# schV2_2.net
KiCad netlist of a schematic drawn in EAGLE
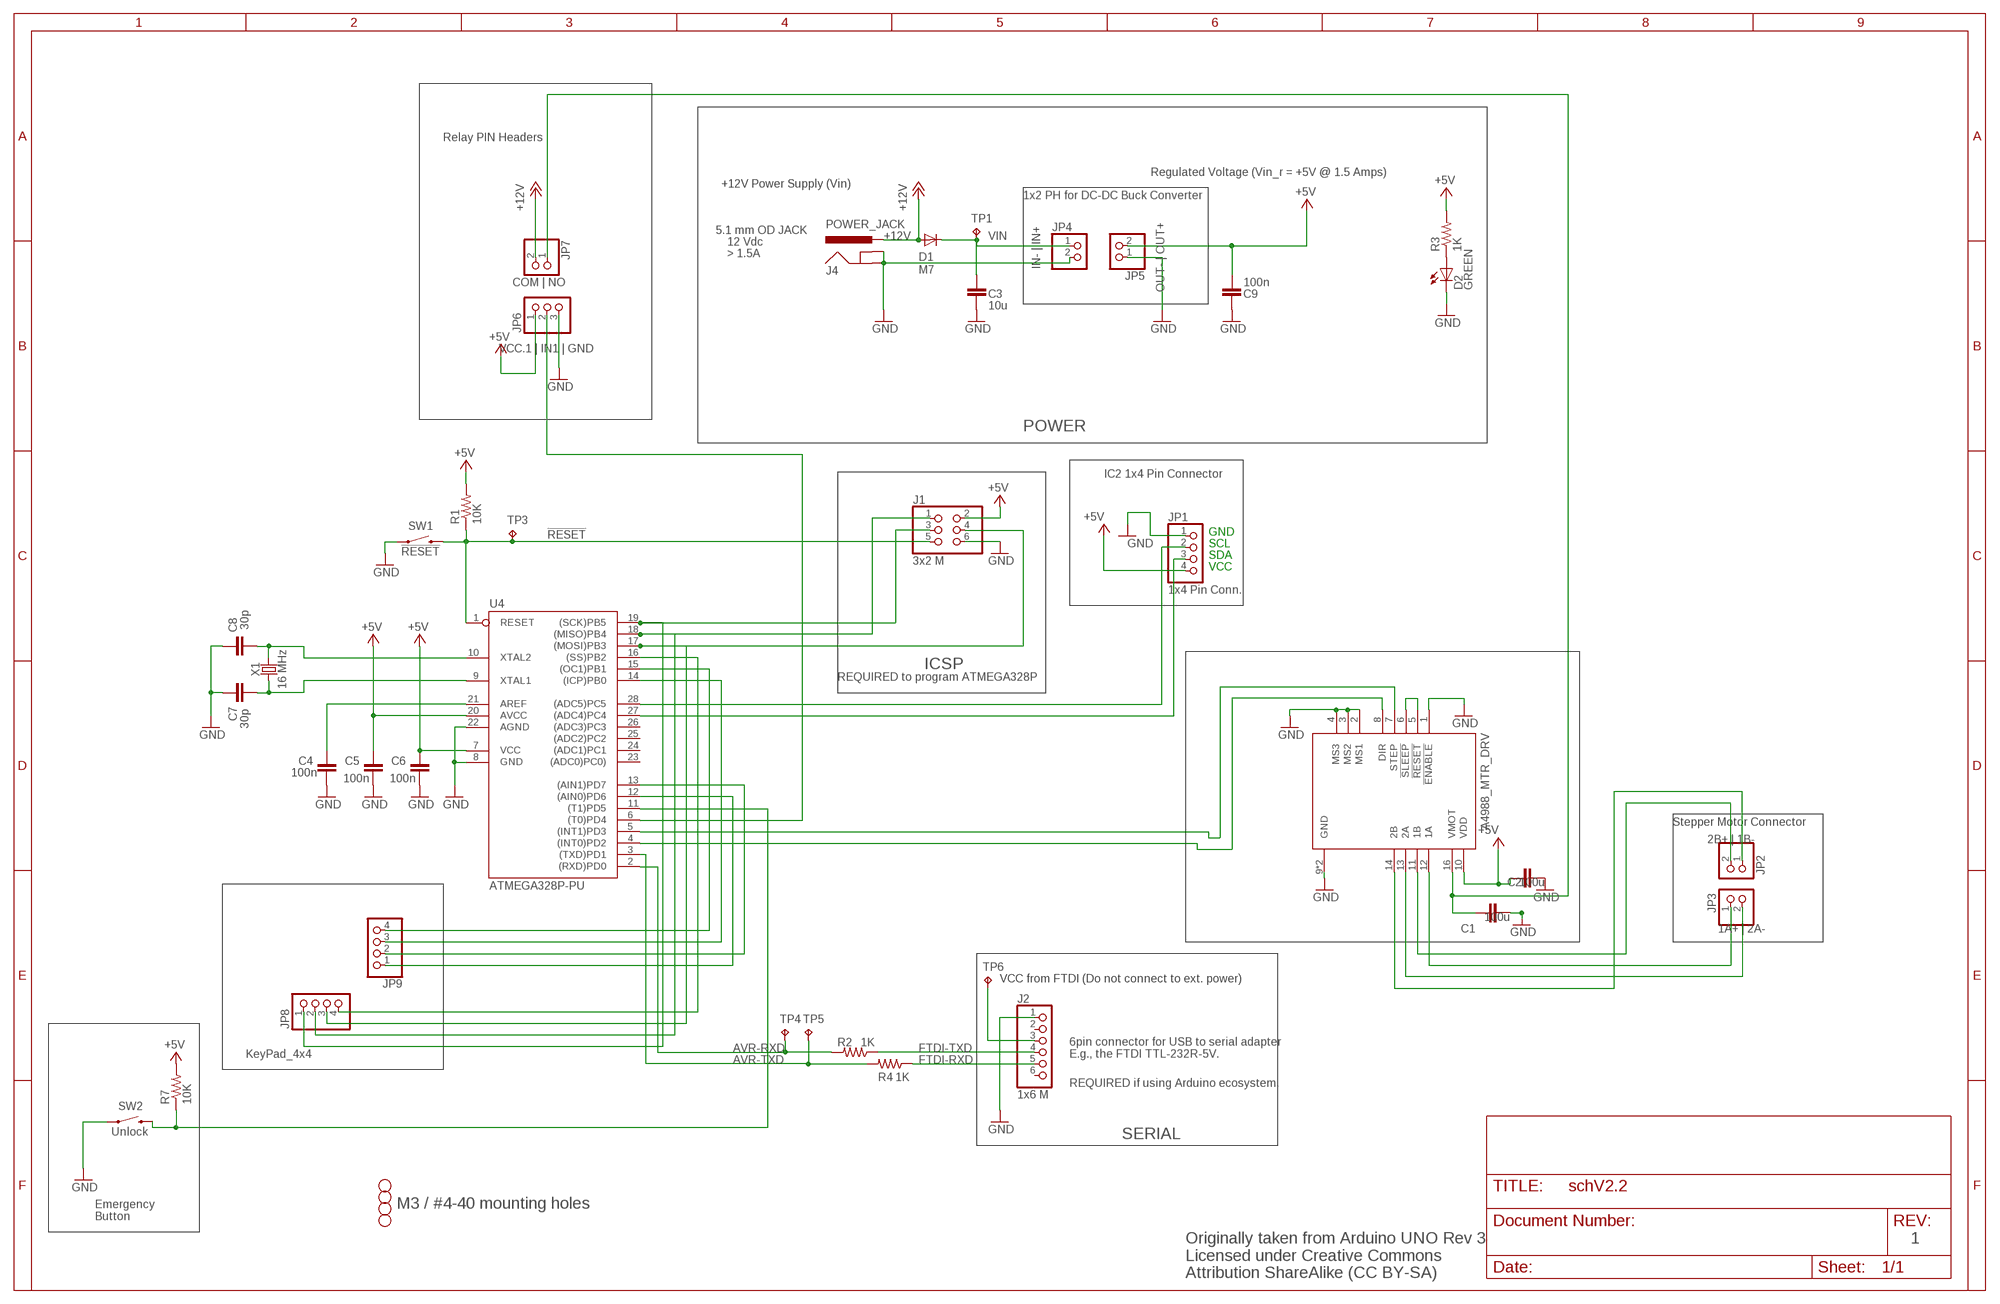
[diagram p0: schematic, sheet 1]

(export (version "E")
  (design (tool "Eeschema 10.0.6"))
  (components
    (comp (ref "A4988_MTR_DRV")
      (value "A4988_STEPPER_MOTOR_DRIVER_CARRIER")
      (footprint "eagle-import:MODULE_A4988_STEPPER_MOTOR_DRIVER_CARRIER")
      (fields (field (name "MF") "Pololu") (field (name "MP") "A4988 STEPPER MOTOR DRIVER CARRIER"))
      (libsource (lib "eagle-import") (part "A4988_STEPPER_MOTOR_DRIVER_CARRIER"))
    )
    (comp (ref "C1")
      (value "100u")
      (footprint "eagle-import:C0805K")
      (fields (field (name "MFR") "Samsung") (field (name "MPN") "CL21B104KBCNNNC"))
      (libsource (lib "eagle-import") (part "C-EUC0805K"))
    )
    (comp (ref "C2")
      (value "100u")
      (footprint "eagle-import:C0805K")
      (fields (field (name "MFR") "Samsung") (field (name "MPN") "CL21B104KBCNNNC"))
      (libsource (lib "eagle-import") (part "C-EUC0805K"))
    )
    (comp (ref "C3")
      (value "10u")
      (footprint "eagle-import:C0805K")
      (fields (field (name "MFR") "Samsung") (field (name "MPN") "CL21A106KOQNNNG"))
      (libsource (lib "eagle-import") (part "C-EUC0805K"))
    )
    (comp (ref "C4")
      (value "100n")
      (footprint "eagle-import:C0805K")
      (fields (field (name "MFR") "Samsung") (field (name "MPN") "CL21B104KBCNNNC"))
      (libsource (lib "eagle-import") (part "C-EUC0805K"))
    )
    (comp (ref "C5")
      (value "100n")
      (footprint "eagle-import:C0805K")
      (fields (field (name "MFR") "Samsung") (field (name "MPN") "CL21B104KBCNNNC"))
      (libsource (lib "eagle-import") (part "C-EUC0805K"))
    )
    (comp (ref "C6")
      (value "100n")
      (footprint "eagle-import:C0805K")
      (fields (field (name "MFR") "Samsung") (field (name "MPN") "CL21B104KBCNNNC"))
      (libsource (lib "eagle-import") (part "C-EUC0805K"))
    )
    (comp (ref "C7")
      (value "30p")
      (footprint "eagle-import:C0805K")
      (fields (field (name "MFR") "Samsung") (field (name "MPN") "CL21C180JBANNNC"))
      (libsource (lib "eagle-import") (part "C-EUC0805K"))
    )
    (comp (ref "C8")
      (value "30p")
      (footprint "eagle-import:C0805K")
      (fields (field (name "MFR") "Samsung") (field (name "MPN") "CL21C300JBANNNC"))
      (libsource (lib "eagle-import") (part "C-EUC0805K"))
    )
    (comp (ref "C9")
      (value "100n")
      (footprint "eagle-import:C0805K")
      (fields (field (name "MFR") "Samsung") (field (name "MPN") "CL21B104KBCNNNC"))
      (libsource (lib "eagle-import") (part "C-EUC0805K"))
    )
    (comp (ref "D1")
      (value "M7")
      (footprint "eagle-import:SMB")
      (fields (field (name "MFR") "SMC Diode") (field (name "MPN") "10BQ030TR"))
      (libsource (lib "eagle-import") (part "DIODE-SMB"))
    )
    (comp (ref "D2")
      (value "GREEN")
      (footprint "eagle-import:CHIP-LED0805")
      (fields (field (name "MFR") "Würth Elektronik") (field (name "MPN") "150080GS75000"))
      (libsource (lib "eagle-import") (part "LEDCHIP-LED0805"))
    )
    (comp (ref "H1")
      (value "STAND-OFF")
      (footprint "eagle-import:STAND-OFF")
      (libsource (lib "eagle-import") (part "STAND-OFF"))
    )
    (comp (ref "H2")
      (value "STAND-OFF")
      (footprint "eagle-import:STAND-OFF")
      (libsource (lib "eagle-import") (part "STAND-OFF"))
    )
    (comp (ref "H3")
      (value "STAND-OFF")
      (footprint "eagle-import:STAND-OFF")
      (libsource (lib "eagle-import") (part "STAND-OFF"))
    )
    (comp (ref "H4")
      (value "STAND-OFF")
      (footprint "eagle-import:STAND-OFF")
      (libsource (lib "eagle-import") (part "STAND-OFF"))
    )
    (comp (ref "J1")
      (value "3x2 M")
      (footprint "eagle-import:2X03")
      (fields (field (name "MFR") "Harwin") (field (name "MPN") "M20-9980345"))
      (libsource (lib "eagle-import") (part "PINHD-2X3"))
    )
    (comp (ref "J2")
      (value "1x6 M")
      (footprint "eagle-import:1X06")
      (fields (field (name "MFR") "Sullins") (field (name "MPN") "PRPC006SAAN-RC"))
      (libsource (lib "eagle-import") (part "PINHD-1X6"))
    )
    (comp (ref "J4")
      (value "POWER_JACK")
      (footprint "eagle-import:POWER_JACK_PTH")
      (fields (field (name "MFR") "CUI") (field (name "MPN") "PJ-202A"))
      (libsource (lib "eagle-import") (part "POWER_JACK"))
    )
    (comp (ref "JP1")
      (value "1x4 Pin Conn.")
      (footprint "eagle-import:1X04")
      (libsource (lib "eagle-import") (part "PINHD-1X4"))
    )
    (comp (ref "JP2")
      (value "2B+ | 1B-")
      (footprint "eagle-import:1X02")
      (libsource (lib "eagle-import") (part "PINHD-1X2"))
    )
    (comp (ref "JP3")
      (value "1A+ | 2A-")
      (footprint "eagle-import:1X02")
      (libsource (lib "eagle-import") (part "PINHD-1X2"))
    )
    (comp (ref "JP4")
      (value "IN- | IN+")
      (footprint "eagle-import:1X02")
      (libsource (lib "eagle-import") (part "PINHD-1X2"))
    )
    (comp (ref "JP5")
      (value "OUT- | OUT+")
      (footprint "eagle-import:1X02")
      (libsource (lib "eagle-import") (part "PINHD-1X2"))
    )
    (comp (ref "JP6")
      (value "VCC.1 | IN1 | GND")
      (footprint "eagle-import:1X03")
      (libsource (lib "eagle-import") (part "PINHD-1X3"))
    )
    (comp (ref "JP7")
      (value "COM | NO")
      (footprint "eagle-import:1X02")
      (libsource (lib "eagle-import") (part "PINHD-1X2"))
    )
    (comp (ref "JP8")
      (value "PINHD-1X4")
      (footprint "eagle-import:1X04")
      (libsource (lib "eagle-import") (part "PINHD-1X4"))
    )
    (comp (ref "JP9")
      (value "PINHD-1X4")
      (footprint "eagle-import:1X04")
      (libsource (lib "eagle-import") (part "PINHD-1X4"))
    )
    (comp (ref "R1")
      (value "10K")
      (footprint "eagle-import:R0805")
      (fields (field (name "MFR") "Yageo") (field (name "MPN") "RC0805FR-0710KL"))
      (libsource (lib "eagle-import") (part "R-US_R0805"))
    )
    (comp (ref "R2")
      (value "1K")
      (footprint "eagle-import:R0805")
      (fields (field (name "MFR") "Yageo") (field (name "MPN") "RC0805FR-071KL"))
      (libsource (lib "eagle-import") (part "R-US_R0805"))
    )
    (comp (ref "R3")
      (value "1K")
      (footprint "eagle-import:R0805")
      (fields (field (name "MFR") "Yageo") (field (name "MPN") "RC0805FR-071KL"))
      (libsource (lib "eagle-import") (part "R-US_R0805"))
    )
    (comp (ref "R4")
      (value "1K")
      (footprint "eagle-import:R0805")
      (fields (field (name "MFR") "Yageo") (field (name "MPN") "RC0805FR-071KL"))
      (libsource (lib "eagle-import") (part "R-US_R0805"))
    )
    (comp (ref "R7")
      (value "10K")
      (footprint "eagle-import:R0805")
      (fields (field (name "MFR") "Yageo") (field (name "MPN") "RC0805FR-0710KL"))
      (libsource (lib "eagle-import") (part "R-US_R0805"))
    )
    (comp (ref "SW1")
      (value "!RESET")
      (footprint "eagle-import:TACTILE_SWITCH_SMD")
      (fields (field (name "MFR") "C&K") (field (name "MPN") "RS-187R05A2-DS MT RT"))
      (libsource (lib "eagle-import") (part "SWITCH-MOMENTARY-2SMD"))
    )
    (comp (ref "SW2")
      (value "Unlock")
      (footprint "eagle-import:TACTILE_SWITCH_SMD")
      (fields (field (name "MFR") "C&K") (field (name "MPN") "RS-187R05A2-DS MT RT"))
      (libsource (lib "eagle-import") (part "SWITCH-MOMENTARY-2SMD"))
    )
    (comp (ref "TP1")
      (value "TPPAD1-13")
      (footprint "eagle-import:P1-13")
      (libsource (lib "eagle-import") (part "TPPAD1-13"))
    )
    (comp (ref "TP3")
      (value "TPPAD1-13")
      (footprint "eagle-import:P1-13")
      (libsource (lib "eagle-import") (part "TPPAD1-13"))
    )
    (comp (ref "TP4")
      (value "TPPAD1-13")
      (footprint "eagle-import:P1-13")
      (libsource (lib "eagle-import") (part "TPPAD1-13"))
    )
    (comp (ref "TP5")
      (value "TPPAD1-13")
      (footprint "eagle-import:P1-13")
      (libsource (lib "eagle-import") (part "TPPAD1-13"))
    )
    (comp (ref "TP6")
      (value "TPPAD1-13")
      (footprint "eagle-import:P1-13")
      (libsource (lib "eagle-import") (part "TPPAD1-13"))
    )
    (comp (ref "U4")
      (value "ATMEGA328P-PU")
      (footprint "eagle-import:DIL28-3")
      (fields (field (name "MFR") "Microchip"))
      (libsource (lib "eagle-import") (part "ATMEGA328P-PU"))
    )
    (comp (ref "X1")
      (value "16 MHz")
      (footprint "eagle-import:HC49UP")
      (fields (field (name "MFR") "ECS") (field (name "MPN") "ECS-160-18-5PX-TR"))
      (libsource (lib "eagle-import") (part "CRYSTALSMD-HC49UP"))
    )
  )
  (nets
    (net (code "1") (name "+5V") (class "Default")
      (node (ref "A4988_MTR_DRV") (pin "10") (pinfunction "VDD_10") (pintype "power_in"))
      (node (ref "C2") (pin "2") (pinfunction "2_2") (pintype "passive"))
      (node (ref "C5") (pin "2") (pinfunction "2_2") (pintype "passive"))
      (node (ref "C6") (pin "2") (pinfunction "2_2") (pintype "passive"))
      (node (ref "C9") (pin "2") (pinfunction "2_2") (pintype "passive"))
      (node (ref "J1") (pin "2") (pinfunction "2_2") (pintype "passive"))
      (node (ref "JP1") (pin "4") (pinfunction "4_4") (pintype "passive"))
      (node (ref "JP5") (pin "2") (pinfunction "2_2") (pintype "passive"))
      (node (ref "JP6") (pin "1") (pinfunction "1_1") (pintype "passive"))
      (node (ref "R1") (pin "2") (pinfunction "2_2") (pintype "passive"))
      (node (ref "R3") (pin "2") (pinfunction "2_2") (pintype "passive"))
      (node (ref "R7") (pin "2") (pinfunction "2_2") (pintype "passive"))
      (node (ref "U4") (pin "20") (pinfunction "AVCC_20") (pintype "power_in"))
      (node (ref "U4") (pin "7") (pinfunction "VCC_7") (pintype "power_in"))
    )
    (net (code "2") (name "+12V") (class "Default")
      (node (ref "D1") (pin "A") (pinfunction "A_A") (pintype "passive"))
      (node (ref "J4") (pin "PWR") (pinfunction "PWR_PWR") (pintype "bidirectional"))
      (node (ref "JP7") (pin "2") (pinfunction "2_2") (pintype "passive"))
    )
    (net (code "3") (name "/AVR-RXD") (class "Default")
      (node (ref "R2") (pin "2") (pinfunction "2_2") (pintype "passive"))
      (node (ref "TP4") (pin "TP") (pinfunction "TP_TP") (pintype "input"))
      (node (ref "U4") (pin "2") (pinfunction "(RXD)PD0_2") (pintype "bidirectional"))
    )
    (net (code "4") (name "/AVR-TXD") (class "Default")
      (node (ref "R4") (pin "2") (pinfunction "2_2") (pintype "passive"))
      (node (ref "TP5") (pin "TP") (pinfunction "TP_TP") (pintype "input"))
      (node (ref "U4") (pin "3") (pinfunction "(TXD)PD1_3") (pintype "bidirectional"))
    )
    (net (code "5") (name "/FTDI-RXD") (class "Default")
      (node (ref "J2") (pin "5") (pinfunction "5_5") (pintype "passive"))
      (node (ref "R4") (pin "1") (pinfunction "1_1") (pintype "passive"))
    )
    (net (code "6") (name "/FTDI-TXD") (class "Default")
      (node (ref "J2") (pin "4") (pinfunction "4_4") (pintype "passive"))
      (node (ref "R2") (pin "1") (pinfunction "1_1") (pintype "passive"))
    )
    (net (code "7") (name "/VIN") (class "Default")
      (node (ref "C3") (pin "1") (pinfunction "1_1") (pintype "passive"))
      (node (ref "D1") (pin "C") (pinfunction "C_C") (pintype "passive"))
      (node (ref "JP4") (pin "1") (pinfunction "1_1") (pintype "passive"))
      (node (ref "TP1") (pin "TP") (pinfunction "TP_TP") (pintype "input"))
    )
    (net (code "8") (name "/~{RESET}") (class "Default")
      (node (ref "J1") (pin "5") (pinfunction "5_5") (pintype "passive"))
      (node (ref "R1") (pin "1") (pinfunction "1_1") (pintype "passive"))
      (node (ref "SW1") (pin "3") (pinfunction "2_3") (pintype "passive"))
      (node (ref "TP3") (pin "TP") (pinfunction "TP_TP") (pintype "input"))
      (node (ref "U4") (pin "1") (pinfunction "RESET_1") (pintype "input"))
    )
    (net (code "9") (name "GND") (class "Default")
      (node (ref "A4988_MTR_DRV") (pin "1") (pinfunction "~{ENABLE}_1") (pintype "input"))
      (node (ref "A4988_MTR_DRV") (pin "15") (pinfunction "GND_15") (pintype "power_in"))
      (node (ref "A4988_MTR_DRV") (pin "2") (pinfunction "MS1_2") (pintype "input"))
      (node (ref "A4988_MTR_DRV") (pin "3") (pinfunction "MS2_3") (pintype "input"))
      (node (ref "A4988_MTR_DRV") (pin "4") (pinfunction "MS3_4") (pintype "input"))
      (node (ref "A4988_MTR_DRV") (pin "9") (pinfunction "GND_9") (pintype "power_in"))
      (node (ref "C1") (pin "1") (pinfunction "1_1") (pintype "passive"))
      (node (ref "C2") (pin "1") (pinfunction "1_1") (pintype "passive"))
      (node (ref "C3") (pin "2") (pinfunction "2_2") (pintype "passive"))
      (node (ref "C4") (pin "1") (pinfunction "1_1") (pintype "passive"))
      (node (ref "C5") (pin "1") (pinfunction "1_1") (pintype "passive"))
      (node (ref "C6") (pin "1") (pinfunction "1_1") (pintype "passive"))
      (node (ref "C7") (pin "2") (pinfunction "2_2") (pintype "passive"))
      (node (ref "C8") (pin "2") (pinfunction "2_2") (pintype "passive"))
      (node (ref "C9") (pin "1") (pinfunction "1_1") (pintype "passive"))
      (node (ref "D2") (pin "C") (pinfunction "C_C") (pintype "passive"))
      (node (ref "J1") (pin "6") (pinfunction "6_6") (pintype "passive"))
      (node (ref "J2") (pin "1") (pinfunction "1_1") (pintype "passive"))
      (node (ref "J4") (pin "GND") (pinfunction "GND_GND") (pintype "bidirectional"))
      (node (ref "J4") (pin "GNDBREAK") (pinfunction "GNDBREAK_GNDBREAK") (pintype "bidirectional"))
      (node (ref "JP1") (pin "1") (pinfunction "1_1") (pintype "passive"))
      (node (ref "JP4") (pin "2") (pinfunction "2_2") (pintype "passive"))
      (node (ref "JP5") (pin "1") (pinfunction "1_1") (pintype "passive"))
      (node (ref "JP6") (pin "3") (pinfunction "3_3") (pintype "passive"))
      (node (ref "SW1") (pin "1") (pinfunction "1_1") (pintype "passive"))
      (node (ref "SW2") (pin "1") (pinfunction "1_1") (pintype "passive"))
      (node (ref "U4") (pin "22") (pinfunction "AGND_22") (pintype "power_in"))
      (node (ref "U4") (pin "8") (pinfunction "GND_8") (pintype "power_in"))
    )
    (net (code "10") (name "Net-(A4988_MTR_DRV-1A)") (class "Default")
      (node (ref "A4988_MTR_DRV") (pin "12") (pinfunction "1A_12") (pintype "output"))
      (node (ref "JP3") (pin "1") (pinfunction "1_1") (pintype "passive"))
    )
    (net (code "11") (name "Net-(A4988_MTR_DRV-1B)") (class "Default")
      (node (ref "A4988_MTR_DRV") (pin "11") (pinfunction "1B_11") (pintype "output"))
      (node (ref "JP2") (pin "2") (pinfunction "2_2") (pintype "passive"))
    )
    (net (code "12") (name "Net-(A4988_MTR_DRV-2A)") (class "Default")
      (node (ref "A4988_MTR_DRV") (pin "13") (pinfunction "2A_13") (pintype "output"))
      (node (ref "JP3") (pin "2") (pinfunction "2_2") (pintype "passive"))
    )
    (net (code "13") (name "Net-(A4988_MTR_DRV-2B)") (class "Default")
      (node (ref "A4988_MTR_DRV") (pin "14") (pinfunction "2B_14") (pintype "output"))
      (node (ref "JP2") (pin "1") (pinfunction "1_1") (pintype "passive"))
    )
    (net (code "14") (name "Net-(A4988_MTR_DRV-DIR)") (class "Default")
      (node (ref "A4988_MTR_DRV") (pin "8") (pinfunction "DIR_8") (pintype "input"))
      (node (ref "U4") (pin "4") (pinfunction "(INT0)PD2_4") (pintype "bidirectional"))
    )
    (net (code "15") (name "Net-(A4988_MTR_DRV-STEP)") (class "Default")
      (node (ref "A4988_MTR_DRV") (pin "7") (pinfunction "STEP_7") (pintype "input"))
      (node (ref "U4") (pin "5") (pinfunction "(INT1)PD3_5") (pintype "bidirectional"))
    )
    (net (code "16") (name "Net-(A4988_MTR_DRV-VMOT)") (class "Default")
      (node (ref "A4988_MTR_DRV") (pin "16") (pinfunction "VMOT_16") (pintype "power_in"))
      (node (ref "C1") (pin "2") (pinfunction "2_2") (pintype "passive"))
      (node (ref "JP7") (pin "1") (pinfunction "1_1") (pintype "passive"))
    )
    (net (code "17") (name "Net-(A4988_MTR_DRV-~{RESET})") (class "Default")
      (node (ref "A4988_MTR_DRV") (pin "5") (pinfunction "~{RESET}_5") (pintype "input"))
      (node (ref "A4988_MTR_DRV") (pin "6") (pinfunction "~{SLEEP}_6") (pintype "input"))
    )
    (net (code "18") (name "Net-(D2-PadA)") (class "Default")
      (node (ref "D2") (pin "A") (pinfunction "A_A") (pintype "passive"))
      (node (ref "R3") (pin "1") (pinfunction "1_1") (pintype "passive"))
    )
    (net (code "19") (name "Net-(J2-Pad3)") (class "Default")
      (node (ref "J2") (pin "3") (pinfunction "3_3") (pintype "passive"))
      (node (ref "TP6") (pin "TP") (pinfunction "TP_TP") (pintype "input"))
    )
    (net (code "20") (name "Net-(SW2-2)") (class "Default")
      (node (ref "R7") (pin "1") (pinfunction "1_1") (pintype "passive"))
      (node (ref "SW2") (pin "3") (pinfunction "2_3") (pintype "passive"))
      (node (ref "U4") (pin "11") (pinfunction "(T1)PD5_11") (pintype "bidirectional"))
    )
    (net (code "21") (name "Net-(U4-(ADC4)PC4)") (class "Default")
      (node (ref "JP1") (pin "3") (pinfunction "3_3") (pintype "passive"))
      (node (ref "U4") (pin "27") (pinfunction "(ADC4)PC4_27") (pintype "bidirectional"))
    )
    (net (code "22") (name "Net-(U4-(ADC5)PC5)") (class "Default")
      (node (ref "JP1") (pin "2") (pinfunction "2_2") (pintype "passive"))
      (node (ref "U4") (pin "28") (pinfunction "(ADC5)PC5_28") (pintype "bidirectional"))
    )
    (net (code "23") (name "Net-(U4-(AIN0)PD6)") (class "Default")
      (node (ref "JP9") (pin "1") (pinfunction "1_1") (pintype "passive"))
      (node (ref "U4") (pin "12") (pinfunction "(AIN0)PD6_12") (pintype "bidirectional"))
    )
    (net (code "24") (name "Net-(U4-(AIN1)PD7)") (class "Default")
      (node (ref "JP9") (pin "2") (pinfunction "2_2") (pintype "passive"))
      (node (ref "U4") (pin "13") (pinfunction "(AIN1)PD7_13") (pintype "bidirectional"))
    )
    (net (code "25") (name "Net-(U4-(ICP)PB0)") (class "Default")
      (node (ref "JP9") (pin "3") (pinfunction "3_3") (pintype "passive"))
      (node (ref "U4") (pin "14") (pinfunction "(ICP)PB0_14") (pintype "bidirectional"))
    )
    (net (code "26") (name "Net-(U4-(MISO)PB4)") (class "Default")
      (node (ref "J1") (pin "1") (pinfunction "1_1") (pintype "passive"))
      (node (ref "JP8") (pin "2") (pinfunction "2_2") (pintype "passive"))
      (node (ref "U4") (pin "18") (pinfunction "(MISO)PB4_18") (pintype "bidirectional"))
    )
    (net (code "27") (name "Net-(U4-(MOSI)PB3)") (class "Default")
      (node (ref "J1") (pin "4") (pinfunction "4_4") (pintype "passive"))
      (node (ref "JP8") (pin "3") (pinfunction "3_3") (pintype "passive"))
      (node (ref "U4") (pin "17") (pinfunction "(MOSI)PB3_17") (pintype "bidirectional"))
    )
    (net (code "28") (name "Net-(U4-(OC1)PB1)") (class "Default")
      (node (ref "JP9") (pin "4") (pinfunction "4_4") (pintype "passive"))
      (node (ref "U4") (pin "15") (pinfunction "(OC1)PB1_15") (pintype "bidirectional"))
    )
    (net (code "29") (name "Net-(U4-(SCK)PB5)") (class "Default")
      (node (ref "J1") (pin "3") (pinfunction "3_3") (pintype "passive"))
      (node (ref "JP8") (pin "1") (pinfunction "1_1") (pintype "passive"))
      (node (ref "U4") (pin "19") (pinfunction "(SCK)PB5_19") (pintype "bidirectional"))
    )
    (net (code "30") (name "Net-(U4-(SS)PB2)") (class "Default")
      (node (ref "JP8") (pin "4") (pinfunction "4_4") (pintype "passive"))
      (node (ref "U4") (pin "16") (pinfunction "(SS)PB2_16") (pintype "bidirectional"))
    )
    (net (code "31") (name "Net-(U4-(T0)PD4)") (class "Default")
      (node (ref "JP6") (pin "2") (pinfunction "2_2") (pintype "passive"))
      (node (ref "U4") (pin "6") (pinfunction "(T0)PD4_6") (pintype "bidirectional"))
    )
    (net (code "32") (name "Net-(U4-AREF)") (class "Default")
      (node (ref "C4") (pin "2") (pinfunction "2_2") (pintype "passive"))
      (node (ref "U4") (pin "21") (pinfunction "AREF_21") (pintype "passive"))
    )
    (net (code "33") (name "Net-(U4-XTAL1)") (class "Default")
      (node (ref "C7") (pin "1") (pinfunction "1_1") (pintype "passive"))
      (node (ref "U4") (pin "9") (pinfunction "XTAL1_9") (pintype "bidirectional"))
      (node (ref "X1") (pin "1") (pinfunction "1_1") (pintype "passive"))
    )
    (net (code "34") (name "Net-(U4-XTAL2)") (class "Default")
      (node (ref "C8") (pin "1") (pinfunction "1_1") (pintype "passive"))
      (node (ref "U4") (pin "10") (pinfunction "XTAL2_10") (pintype "bidirectional"))
      (node (ref "X1") (pin "2") (pinfunction "2_2") (pintype "passive"))
    )
    (net (code "35") (name "unconnected-(J2-Pad2)") (class "Default")
      (node (ref "J2") (pin "2") (pinfunction "2_2") (pintype "passive"))
    )
    (net (code "36") (name "unconnected-(J2-Pad6)") (class "Default")
      (node (ref "J2") (pin "6") (pinfunction "6_6") (pintype "passive"))
    )
    (net (code "37") (name "unconnected-(U4-(ADC0)PC0)-Pad23)") (class "Default")
      (node (ref "U4") (pin "23") (pinfunction "(ADC0)PC0)_23") (pintype "bidirectional"))
    )
    (net (code "38") (name "unconnected-(U4-(ADC1)PC1-Pad24)") (class "Default")
      (node (ref "U4") (pin "24") (pinfunction "(ADC1)PC1_24") (pintype "bidirectional"))
    )
    (net (code "39") (name "unconnected-(U4-(ADC2)PC2-Pad25)") (class "Default")
      (node (ref "U4") (pin "25") (pinfunction "(ADC2)PC2_25") (pintype "bidirectional"))
    )
    (net (code "40") (name "unconnected-(U4-(ADC3)PC3-Pad26)") (class "Default")
      (node (ref "U4") (pin "26") (pinfunction "(ADC3)PC3_26") (pintype "bidirectional"))
    )
  )
)
